# SD_CARD.net
KiCad netlist of a schematic drawn in Altium Designer
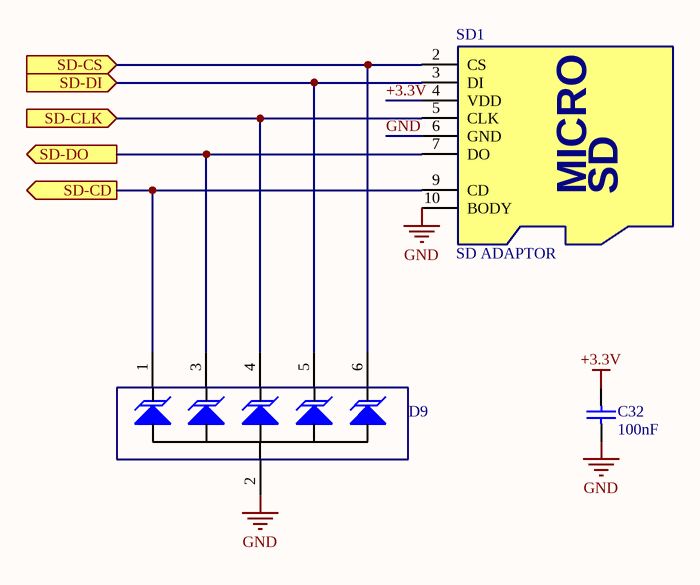
[diagram p0: SD CARD.SchDoc]

(export (version "E")
  (design (tool "Eeschema 10.0.6"))
  (components
    (comp (ref "C32")
      (value "100nF")
      (footprint "C603")
      (description "Capacitor")
      (fields (field (name "DESIGNER") "Parsa Malekpour"))
      (libsource (lib "UserPKG") (part "Cap"))
    )
    (comp (ref "D9")
      (value "SMF05C")
      (footprint "SOT-363")
      (description "TVS Diode Array  For ESD and Latch-Up Protection")
      (libsource (lib "UserPKG") (part "SMF05C"))
    )
    (comp (ref "SD1")
      (value "SD ADAPTOR")
      (footprint "MICRO-SD")
      (description "uSD ADAPTOR")
      (fields (field (name "DESIGNER") "Parsa Malekpour") (field (name "EMAIL") "malekpour.parsa@Gmail.com"))
      (libsource (lib "UserPKG") (part "uSD"))
    )
  )
  (nets
    (net (code "1") (name "+3.3V") (class "Default")
      (node (ref "C32") (pin "2") (pinfunction "2_2") (pintype "passive"))
      (node (ref "SD1") (pin "4") (pinfunction "VDD_4") (pintype "passive"))
    )
    (net (code "2") (name "/SD-CD") (class "Default")
      (node (ref "D9") (pin "1") (pinfunction "K_1") (pintype "passive"))
      (node (ref "SD1") (pin "9") (pinfunction "CD_9") (pintype "passive"))
    )
    (net (code "3") (name "/SD-CLK") (class "Default")
      (node (ref "D9") (pin "4") (pinfunction "K_4") (pintype "passive"))
      (node (ref "SD1") (pin "5") (pinfunction "CLK_5") (pintype "passive"))
    )
    (net (code "4") (name "/SD-CS") (class "Default")
      (node (ref "D9") (pin "6") (pinfunction "K_6") (pintype "passive"))
      (node (ref "SD1") (pin "2") (pinfunction "CS_2") (pintype "passive"))
    )
    (net (code "5") (name "/SD-DI") (class "Default")
      (node (ref "D9") (pin "5") (pinfunction "K_5") (pintype "passive"))
      (node (ref "SD1") (pin "3") (pinfunction "DI_3") (pintype "passive"))
    )
    (net (code "6") (name "/SD-DO") (class "Default")
      (node (ref "D9") (pin "3") (pinfunction "K_3") (pintype "passive"))
      (node (ref "SD1") (pin "7") (pinfunction "DO_7") (pintype "passive"))
    )
    (net (code "7") (name "GND") (class "Default")
      (node (ref "C32") (pin "1") (pinfunction "1_1") (pintype "passive"))
      (node (ref "D9") (pin "2") (pinfunction "A_2") (pintype "passive"))
      (node (ref "SD1") (pin "10") (pinfunction "BODY_10") (pintype "passive"))
      (node (ref "SD1") (pin "6") (pinfunction "GND_6") (pintype "passive"))
    )
    (net (code "8") (name "unconnected-(SD1-DAT1-Pad8)") (class "Default")
      (node (ref "SD1") (pin "8") (pinfunction "DAT1_8") (pintype "passive"))
    )
    (net (code "9") (name "unconnected-(SD1-DAT2-Pad1)") (class "Default")
      (node (ref "SD1") (pin "1") (pinfunction "DAT2_1") (pintype "passive"))
    )
  )
)
